# arpie_control-tab.net
KiCad netlist of a schematic drawn in EAGLE
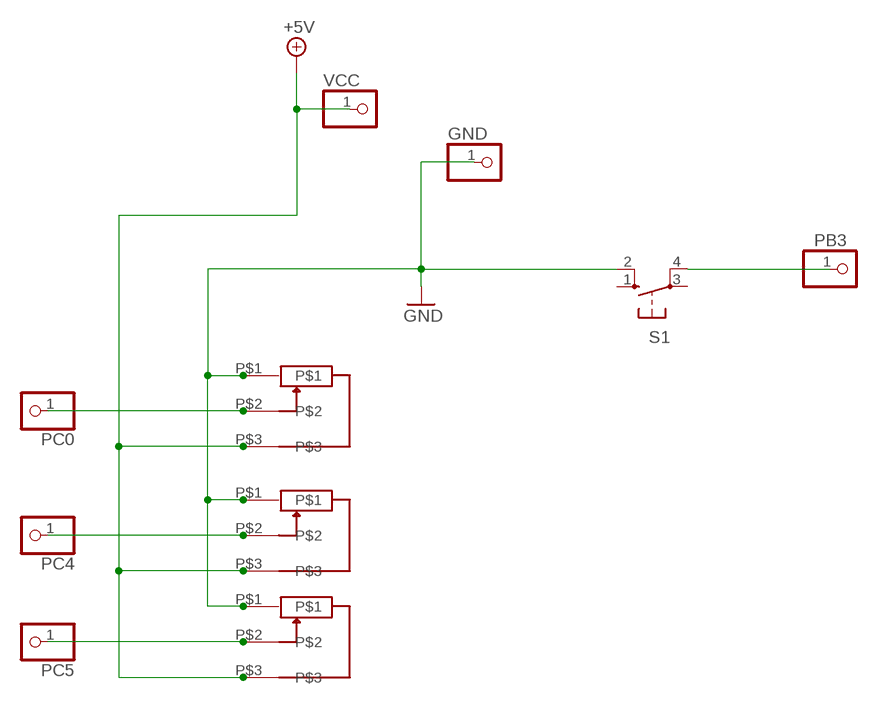
[diagram p0: schematic, sheet 1]

(export (version "E")
  (design (tool "Eeschema 10.0.6"))
  (components
    (comp (ref "GND")
      (value "PINHD-1X1")
      (footprint "eagle-import:1X01")
      (libsource (lib "eagle-import") (part "PINHD-1X1"))
    )
    (comp (ref "PB3")
      (value "PINHD-1X1")
      (footprint "eagle-import:1X01")
      (libsource (lib "eagle-import") (part "PINHD-1X1"))
    )
    (comp (ref "PC0")
      (value "PINHD-1X1")
      (footprint "eagle-import:1X01")
      (libsource (lib "eagle-import") (part "PINHD-1X1"))
    )
    (comp (ref "PC4")
      (value "PINHD-1X1")
      (footprint "eagle-import:1X01")
      (libsource (lib "eagle-import") (part "PINHD-1X1"))
    )
    (comp (ref "PC5")
      (value "PINHD-1X1")
      (footprint "eagle-import:1X01")
      (libsource (lib "eagle-import") (part "PINHD-1X1"))
    )
    (comp (ref "S1")
      (value "10-XX")
      (footprint "eagle-import:B3F-10XX")
      (libsource (lib "eagle-import") (part "10-XX"))
    )
    (comp (ref "U$1")
      (value "PCBMOUNTPOT")
      (footprint "eagle-import:PCBMOUNTPOT")
      (libsource (lib "eagle-import") (part "PCBMOUNTPOT"))
    )
    (comp (ref "U$2")
      (value "PCBMOUNTPOT")
      (footprint "eagle-import:PCBMOUNTPOT")
      (libsource (lib "eagle-import") (part "PCBMOUNTPOT"))
    )
    (comp (ref "U$3")
      (value "PCBMOUNTPOT")
      (footprint "eagle-import:PCBMOUNTPOT")
      (libsource (lib "eagle-import") (part "PCBMOUNTPOT"))
    )
    (comp (ref "VCC")
      (value "PINHD-1X1")
      (footprint "eagle-import:1X01")
      (libsource (lib "eagle-import") (part "PINHD-1X1"))
    )
  )
  (nets
    (net (code "1") (name "+5V") (class "Default")
      (node (ref "U$1") (pin "P$3") (pinfunction "P$3_P$3") (pintype "bidirectional"))
      (node (ref "U$2") (pin "P$3") (pinfunction "P$3_P$3") (pintype "bidirectional"))
      (node (ref "U$3") (pin "P$3") (pinfunction "P$3_P$3") (pintype "bidirectional"))
      (node (ref "VCC") (pin "1") (pinfunction "1_1") (pintype "passive"))
    )
    (net (code "2") (name "GND") (class "Default")
      (node (ref "GND") (pin "1") (pinfunction "1_1") (pintype "passive"))
      (node (ref "S1") (pin "2") (pinfunction "S1_2") (pintype "passive"))
      (node (ref "U$1") (pin "P$1") (pinfunction "P$1_P$1") (pintype "bidirectional"))
      (node (ref "U$2") (pin "P$1") (pinfunction "P$1_P$1") (pintype "bidirectional"))
      (node (ref "U$3") (pin "P$1") (pinfunction "P$1_P$1") (pintype "bidirectional"))
    )
    (net (code "3") (name "Net-(PC0-Pad1)") (class "Default")
      (node (ref "PC0") (pin "1") (pinfunction "1_1") (pintype "passive"))
      (node (ref "U$1") (pin "P$2") (pinfunction "P$2_P$2") (pintype "bidirectional"))
    )
    (net (code "4") (name "Net-(PC4-Pad1)") (class "Default")
      (node (ref "PC4") (pin "1") (pinfunction "1_1") (pintype "passive"))
      (node (ref "U$2") (pin "P$2") (pinfunction "P$2_P$2") (pintype "bidirectional"))
    )
    (net (code "5") (name "Net-(PC5-Pad1)") (class "Default")
      (node (ref "PC5") (pin "1") (pinfunction "1_1") (pintype "passive"))
      (node (ref "U$3") (pin "P$2") (pinfunction "P$2_P$2") (pintype "bidirectional"))
    )
    (net (code "6") (name "Net-(S1-P1)") (class "Default")
      (node (ref "PB3") (pin "1") (pinfunction "1_1") (pintype "passive"))
      (node (ref "S1") (pin "4") (pinfunction "P1_4") (pintype "passive"))
    )
    (net (code "7") (name "unconnected-(S1-P-Pad3)") (class "Default")
      (node (ref "S1") (pin "3") (pinfunction "P_3") (pintype "passive"))
    )
    (net (code "8") (name "unconnected-(S1-S-Pad1)") (class "Default")
      (node (ref "S1") (pin "1") (pinfunction "S_1") (pintype "passive"))
    )
  )
)
